# WifiModule.net
KiCad netlist of a schematic drawn in Altium Designer
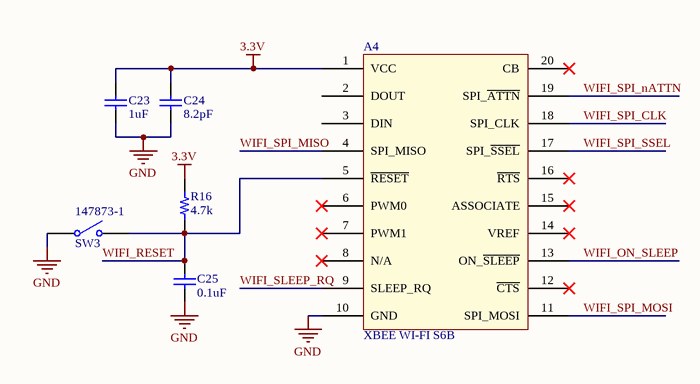
[diagram p0: WifiModule.SchDoc]

(export (version "E")
  (design (tool "Eeschema 10.0.6"))
  (components
    (comp (ref "A4")
      (value "XBEE WI-FI S6B")
      (footprint "Xbee_TH")
      (description "Module Wifi")
      (fields (field (name "MANUFACTURER") "Digi International") (field (name "PART_NUMBER") "XB2B-WFST-001"))
      (libsource (lib "Other") (part "XBEE WI-FI S6B"))
    )
    (comp (ref "C23")
      (value "1uF")
      (footprint "Capacitors:C0603")
      (description "1uF ceramic capacitor")
      (fields (field (name "MANUFACTURER") "TDK Corporation") (field (name "TOLERANCE") "20%"))
      (libsource (lib "Capacitors") (part "CAP CER 0603 1uF 25V X7R 20%"))
    )
    (comp (ref "C24")
      (value "8.2pF")
      (footprint "C0603")
      (description "8.2pF 50V Ceramic Capacitor C0G, NP0 0603")
      (fields
        (field (name "MANUFACTURER") "Murata-Electronics-North-America")
        (field (name "PART_NUMBER") "GCM1885C1H8R2DA16D")
      )
      (libsource (lib "Capacitors") (part "CAP CER 0603 8.2pF 50V COG ±0.5pF"))
    )
    (comp (ref "C25")
      (value "0.1uF")
      (footprint "Capacitors:C0603")
      (description "0.1uF ceramic capacitor")
      (fields (field (name "MANUFACTURER") "TDK Corporation") (field (name "TOLERANCE") "10%"))
      (libsource (lib "Capacitors") (part "CAP CER 0603 0.1uF 50V C0G 10%"))
    )
    (comp (ref "R16")
      (value "4.7k")
      (footprint "Resistors:R0603")
      (description "4.7 kOhms resistor")
      (fields (field (name "PART_NUMBER") "CRCW06034K70JNEA") (field (name "MANUFACTURER") "Vishay"))
      (libsource (lib "Resistors") (part "RES 0603 4.7k 5% 0.1W"))
    )
    (comp (ref "SW3")
      (value "147873-1")
      (footprint "Other:147873")
      (description "Pushbutton switch SPST, 2 pins")
      (fields (field (name "MANUFACTURER") "TE Connectivity"))
      (libsource (lib "Other") (part "147873-1"))
    )
  )
  (nets
    (net (code "1") (name "/WIFI_ON_SLEEP") (class "Default")
      (node (ref "A4") (pin "13") (pinfunction "ON_~{SLEEP}_13") (pintype "passive"))
    )
    (net (code "2") (name "/WIFI_RESET") (class "Default")
      (node (ref "A4") (pin "5") (pinfunction "~{RESET}_5") (pintype "passive"))
      (node (ref "C25") (pin "2") (pinfunction "2_2") (pintype "passive"))
      (node (ref "R16") (pin "1") (pinfunction "1_1") (pintype "passive"))
      (node (ref "SW3") (pin "2") (pinfunction "NO_2") (pintype "passive"))
    )
    (net (code "3") (name "/WIFI_SLEEP_RQ") (class "Default")
      (node (ref "A4") (pin "9") (pinfunction "SLEEP_RQ_9") (pintype "passive"))
    )
    (net (code "4") (name "/WIFI_SPI_CLK") (class "Default")
      (node (ref "A4") (pin "18") (pinfunction "SPI_CLK_18") (pintype "passive"))
    )
    (net (code "5") (name "/WIFI_SPI_MISO") (class "Default")
      (node (ref "A4") (pin "4") (pinfunction "SPI_MISO_4") (pintype "passive"))
    )
    (net (code "6") (name "/WIFI_SPI_MOSI") (class "Default")
      (node (ref "A4") (pin "11") (pinfunction "SPI_MOSI_11") (pintype "passive"))
    )
    (net (code "7") (name "/WIFI_SPI_SSEL") (class "Default")
      (node (ref "A4") (pin "17") (pinfunction "SPI_~{SSEL}_17") (pintype "passive"))
    )
    (net (code "8") (name "/WIFI_SPI_nATTN") (class "Default")
      (node (ref "A4") (pin "19") (pinfunction "SPI_~{ATTN}_19") (pintype "passive"))
    )
    (net (code "9") (name "3.3V") (class "Default")
      (node (ref "A4") (pin "1") (pinfunction "VCC_1") (pintype "passive"))
      (node (ref "C23") (pin "2") (pinfunction "2_2") (pintype "passive"))
      (node (ref "C24") (pin "2") (pinfunction "2_2") (pintype "passive"))
      (node (ref "R16") (pin "2") (pinfunction "2_2") (pintype "passive"))
    )
    (net (code "10") (name "GND") (class "Default")
      (node (ref "A4") (pin "10") (pinfunction "GND_10") (pintype "passive"))
      (node (ref "C23") (pin "1") (pinfunction "1_1") (pintype "passive"))
      (node (ref "C24") (pin "1") (pinfunction "1_1") (pintype "passive"))
      (node (ref "C25") (pin "1") (pinfunction "1_1") (pintype "passive"))
      (node (ref "SW3") (pin "1") (pinfunction "COMMON_1") (pintype "passive"))
    )
    (net (code "11") (name "unconnected-(A4-ASSOCIATE-Pad15)") (class "Default")
      (node (ref "A4") (pin "15") (pinfunction "ASSOCIATE_15") (pintype "passive+no_connect"))
    )
    (net (code "12") (name "unconnected-(A4-CB-Pad20)") (class "Default")
      (node (ref "A4") (pin "20") (pinfunction "CB_20") (pintype "passive+no_connect"))
    )
    (net (code "13") (name "unconnected-(A4-DIN-Pad3)") (class "Default")
      (node (ref "A4") (pin "3") (pinfunction "DIN_3") (pintype "passive"))
    )
    (net (code "14") (name "unconnected-(A4-DOUT-Pad2)") (class "Default")
      (node (ref "A4") (pin "2") (pinfunction "DOUT_2") (pintype "passive"))
    )
    (net (code "15") (name "unconnected-(A4-N{slash}A-Pad8)") (class "Default")
      (node (ref "A4") (pin "8") (pinfunction "N/A_8") (pintype "passive+no_connect"))
    )
    (net (code "16") (name "unconnected-(A4-PWM0-Pad6)") (class "Default")
      (node (ref "A4") (pin "6") (pinfunction "PWM0_6") (pintype "passive+no_connect"))
    )
    (net (code "17") (name "unconnected-(A4-PWM1-Pad7)") (class "Default")
      (node (ref "A4") (pin "7") (pinfunction "PWM1_7") (pintype "passive+no_connect"))
    )
    (net (code "18") (name "unconnected-(A4-VREF-Pad14)") (class "Default")
      (node (ref "A4") (pin "14") (pinfunction "VREF_14") (pintype "passive+no_connect"))
    )
    (net (code "19") (name "unconnected-(A4-~{CTS}-Pad12)") (class "Default")
      (node (ref "A4") (pin "12") (pinfunction "~{CTS}_12") (pintype "passive+no_connect"))
    )
    (net (code "20") (name "unconnected-(A4-~{RTS}-Pad16)") (class "Default")
      (node (ref "A4") (pin "16") (pinfunction "~{RTS}_16") (pintype "passive+no_connect"))
    )
  )
)
